# attiny45.net
KiCad netlist of a schematic drawn in EAGLE
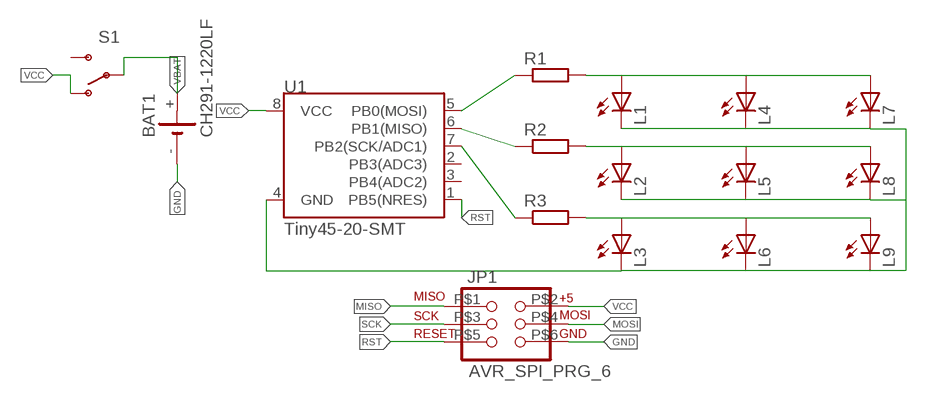
[diagram p0: schematic, sheet 1]

(export (version "E")
  (design (tool "Eeschema 10.0.6"))
  (components
    (comp (ref "BAT1")
      (value "CH291-1220LF")
      (footprint "eagle-import:CH291-1220LF")
      (libsource (lib "eagle-import") (part "CH291-1220LF"))
    )
    (comp (ref "JP1")
      (value "AVR_SPI_PRG_6")
      (footprint "eagle-import:2X3_SMD_PAD")
      (libsource (lib "eagle-import") (part "AVR_SPI_PRG_6"))
    )
    (comp (ref "L1")
      (value "LEDSML1206")
      (footprint "eagle-import:SML1206")
      (libsource (lib "eagle-import") (part "LEDSML1206"))
    )
    (comp (ref "L2")
      (value "LEDSML1206")
      (footprint "eagle-import:SML1206")
      (libsource (lib "eagle-import") (part "LEDSML1206"))
    )
    (comp (ref "L3")
      (value "LEDSML1206")
      (footprint "eagle-import:SML1206")
      (libsource (lib "eagle-import") (part "LEDSML1206"))
    )
    (comp (ref "L4")
      (value "LEDSML1206")
      (footprint "eagle-import:SML1206")
      (libsource (lib "eagle-import") (part "LEDSML1206"))
    )
    (comp (ref "L5")
      (value "LEDSML1206")
      (footprint "eagle-import:SML1206")
      (libsource (lib "eagle-import") (part "LEDSML1206"))
    )
    (comp (ref "L6")
      (value "LEDSML1206")
      (footprint "eagle-import:SML1206")
      (libsource (lib "eagle-import") (part "LEDSML1206"))
    )
    (comp (ref "L7")
      (value "LEDSML1206")
      (footprint "eagle-import:SML1206")
      (libsource (lib "eagle-import") (part "LEDSML1206"))
    )
    (comp (ref "L8")
      (value "LEDSML1206")
      (footprint "eagle-import:SML1206")
      (libsource (lib "eagle-import") (part "LEDSML1206"))
    )
    (comp (ref "L9")
      (value "LEDSML1206")
      (footprint "eagle-import:SML1206")
      (libsource (lib "eagle-import") (part "LEDSML1206"))
    )
    (comp (ref "R1")
      (value "R-EU_M0805")
      (footprint "eagle-import:M0805")
      (libsource (lib "eagle-import") (part "R-EU_M0805"))
    )
    (comp (ref "R2")
      (value "R-EU_M0805")
      (footprint "eagle-import:M0805")
      (libsource (lib "eagle-import") (part "R-EU_M0805"))
    )
    (comp (ref "R3")
      (value "R-EU_M0805")
      (footprint "eagle-import:M0805")
      (libsource (lib "eagle-import") (part "R-EU_M0805"))
    )
    (comp (ref "S1")
      (value "SWITCH-SPDT-SMD-A")
      (footprint "eagle-import:SWITCH-SPST-SMD-A")
      (libsource (lib "eagle-import") (part "SWITCH-SPDT-SMD-A"))
    )
    (comp (ref "U1")
      (value "Tiny45-20-SMT")
      (footprint "eagle-import:SO08-EIAJ")
      (libsource (lib "eagle-import") (part "ATTINY45TINY45-20-SMT"))
    )
  )
  (nets
    (net (code "1") (name "GND") (class "Default")
      (node (ref "BAT1") (pin "-") (pinfunction "-_-") (pintype "passive"))
      (node (ref "JP1") (pin "P$6") (pinfunction "6_P$6") (pintype "passive"))
      (node (ref "L1") (pin "C") (pinfunction "C_C") (pintype "passive"))
      (node (ref "L2") (pin "C") (pinfunction "C_C") (pintype "passive"))
      (node (ref "L3") (pin "C") (pinfunction "C_C") (pintype "passive"))
      (node (ref "L4") (pin "C") (pinfunction "C_C") (pintype "passive"))
      (node (ref "L5") (pin "C") (pinfunction "C_C") (pintype "passive"))
      (node (ref "L6") (pin "C") (pinfunction "C_C") (pintype "passive"))
      (node (ref "L7") (pin "C") (pinfunction "C_C") (pintype "passive"))
      (node (ref "L8") (pin "C") (pinfunction "C_C") (pintype "passive"))
      (node (ref "L9") (pin "C") (pinfunction "C_C") (pintype "passive"))
      (node (ref "U1") (pin "4") (pinfunction "GND_4") (pintype "bidirectional"))
    )
    (net (code "2") (name "MISO") (class "Default")
      (node (ref "JP1") (pin "P$1") (pinfunction "1_P$1") (pintype "passive"))
      (node (ref "R2") (pin "1") (pinfunction "1_1") (pintype "passive"))
      (node (ref "U1") (pin "6") (pinfunction "PB1(MISO)_6") (pintype "bidirectional"))
    )
    (net (code "3") (name "MOSI") (class "Default")
      (node (ref "JP1") (pin "P$4") (pinfunction "4_P$4") (pintype "passive"))
      (node (ref "R1") (pin "1") (pinfunction "1_1") (pintype "passive"))
      (node (ref "U1") (pin "5") (pinfunction "PB0(MOSI)_5") (pintype "bidirectional"))
    )
    (net (code "4") (name "Net-(L1-PadA)") (class "Default")
      (node (ref "L1") (pin "A") (pinfunction "A_A") (pintype "passive"))
      (node (ref "L4") (pin "A") (pinfunction "A_A") (pintype "passive"))
      (node (ref "L7") (pin "A") (pinfunction "A_A") (pintype "passive"))
      (node (ref "R1") (pin "2") (pinfunction "2_2") (pintype "passive"))
    )
    (net (code "5") (name "Net-(L2-PadA)") (class "Default")
      (node (ref "L2") (pin "A") (pinfunction "A_A") (pintype "passive"))
      (node (ref "L5") (pin "A") (pinfunction "A_A") (pintype "passive"))
      (node (ref "L8") (pin "A") (pinfunction "A_A") (pintype "passive"))
      (node (ref "R2") (pin "2") (pinfunction "2_2") (pintype "passive"))
    )
    (net (code "6") (name "Net-(L3-PadA)") (class "Default")
      (node (ref "L3") (pin "A") (pinfunction "A_A") (pintype "passive"))
      (node (ref "L6") (pin "A") (pinfunction "A_A") (pintype "passive"))
      (node (ref "L9") (pin "A") (pinfunction "A_A") (pintype "passive"))
      (node (ref "R3") (pin "2") (pinfunction "2_2") (pintype "passive"))
    )
    (net (code "7") (name "RST") (class "Default")
      (node (ref "JP1") (pin "P$5") (pinfunction "5_P$5") (pintype "passive"))
      (node (ref "U1") (pin "1") (pinfunction "PB5(NRES)_1") (pintype "bidirectional"))
    )
    (net (code "8") (name "SCK") (class "Default")
      (node (ref "JP1") (pin "P$3") (pinfunction "3_P$3") (pintype "passive"))
      (node (ref "R3") (pin "1") (pinfunction "1_1") (pintype "passive"))
      (node (ref "U1") (pin "7") (pinfunction "PB2(SCK/ADC1)_7") (pintype "bidirectional"))
    )
    (net (code "9") (name "VBAT") (class "Default")
      (node (ref "BAT1") (pin "+") (pinfunction "+_+") (pintype "passive"))
      (node (ref "S1") (pin "2") (pinfunction "P_2") (pintype "passive"))
    )
    (net (code "10") (name "VCC") (class "Default")
      (node (ref "JP1") (pin "P$2") (pinfunction "2_P$2") (pintype "passive"))
      (node (ref "S1") (pin "1") (pinfunction "O_1") (pintype "passive"))
      (node (ref "U1") (pin "8") (pinfunction "VCC_8") (pintype "bidirectional"))
    )
    (net (code "11") (name "unconnected-(S1-S-Pad3)") (class "Default")
      (node (ref "S1") (pin "3") (pinfunction "S_3") (pintype "passive"))
    )
    (net (code "12") (name "unconnected-(U1-PB3(ADC3)-Pad2)") (class "Default")
      (node (ref "U1") (pin "2") (pinfunction "PB3(ADC3)_2") (pintype "bidirectional"))
    )
    (net (code "13") (name "unconnected-(U1-PB4(ADC2)-Pad3)") (class "Default")
      (node (ref "U1") (pin "3") (pinfunction "PB4(ADC2)_3") (pintype "bidirectional"))
    )
  )
)
